# receiver.net
KiCad netlist of a schematic drawn in EAGLE
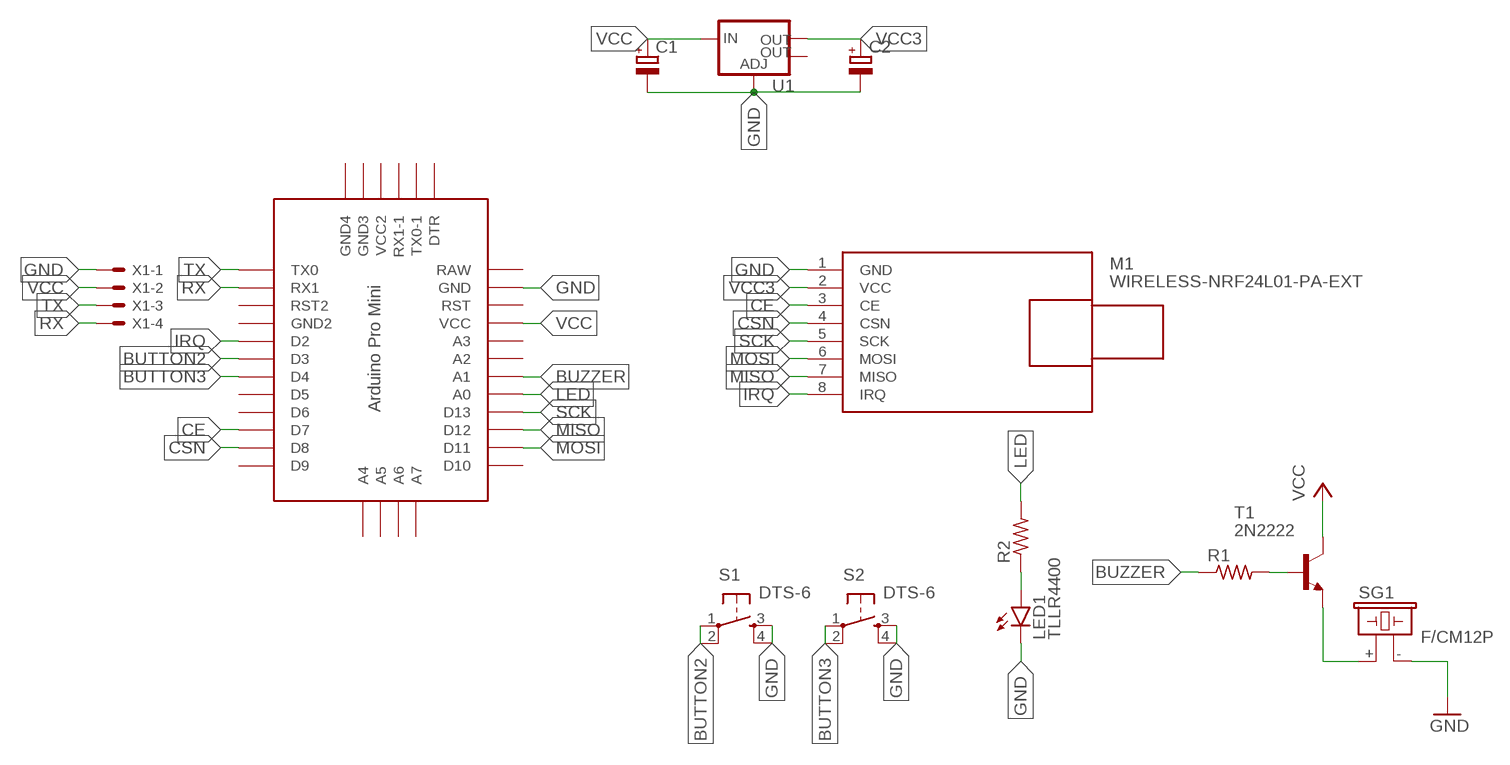
[diagram p0: schematic, sheet 1]

(export (version "E")
  (design (tool "Eeschema 10.0.6"))
  (components
    (comp (ref "C1")
      (value "CPOL-EUE2,5-6E")
      (footprint "eagle-import:E2,5-6E")
      (libsource (lib "eagle-import") (part "CPOL-EUE2,5-6E"))
    )
    (comp (ref "C2")
      (value "CPOL-EUE2,5-6E")
      (footprint "eagle-import:E2,5-6E")
      (libsource (lib "eagle-import") (part "CPOL-EUE2,5-6E"))
    )
    (comp (ref "LED1")
      (value "TLLR4400")
      (footprint "eagle-import:LED3MM")
      (fields (field (name "MF") "VISHAY SEMICONDUCTOR"))
      (libsource (lib "eagle-import") (part "TLLR4400"))
    )
    (comp (ref "M1")
      (value "WIRELESS-NRF24L01-PA-EXT")
      (footprint "eagle-import:WIRELESS-NRF24L01-PA-EXT")
      (libsource (lib "eagle-import") (part "WIRELESS-NRF24L01-PA-EXT"))
    )
    (comp (ref "R1")
      (value "R-US_R0805")
      (footprint "eagle-import:R0805")
      (libsource (lib "eagle-import") (part "R-US_R0805"))
    )
    (comp (ref "R2")
      (value "R-US_R0805")
      (footprint "eagle-import:R0805")
      (libsource (lib "eagle-import") (part "R-US_R0805"))
    )
    (comp (ref "S1")
      (value "DTS-6")
      (footprint "eagle-import:DTS-6")
      (libsource (lib "eagle-import") (part "DTS-6"))
    )
    (comp (ref "S2")
      (value "DTS-6")
      (footprint "eagle-import:DTS-6")
      (libsource (lib "eagle-import") (part "DTS-6"))
    )
    (comp (ref "SG1")
      (value "F/CM12P")
      (footprint "eagle-import:F_CM12P")
      (libsource (lib "eagle-import") (part "F/CM12P"))
    )
    (comp (ref "T1")
      (value "2N2222")
      (footprint "eagle-import:TO92-EBC-OVAL")
      (libsource (lib "eagle-import") (part "2N2222"))
    )
    (comp (ref "U$1")
      (value "PRO-MINI")
      (footprint "eagle-import:PRO-MINI")
      (libsource (lib "eagle-import") (part "PRO-MINI"))
    )
    (comp (ref "U1")
      (value "V_REG_LM1117SOT223")
      (footprint "eagle-import:SOT223")
      (libsource (lib "eagle-import") (part "V_REG_LM1117SOT223"))
    )
    (comp (ref "X1")
      (value "KK-156-4")
      (footprint "eagle-import:KK-156-4")
      (fields (field (name "MF") "MOLEX"))
      (libsource (lib "eagle-import") (part "KK-156-4"))
    )
  )
  (nets
    (net (code "1") (name "/RAW") (class "Default")
      (node (ref "U$1") (pin "RAW") (pinfunction "RAW_RAW") (pintype "power_in"))
    )
    (net (code "2") (name "BUTTON2") (class "Default")
      (node (ref "S1") (pin "1") (pinfunction "1_1") (pintype "passive"))
      (node (ref "S1") (pin "2") (pinfunction "2_2") (pintype "passive"))
      (node (ref "U$1") (pin "D3") (pinfunction "D3_D3") (pintype "bidirectional"))
    )
    (net (code "3") (name "BUTTON3") (class "Default")
      (node (ref "S2") (pin "1") (pinfunction "1_1") (pintype "passive"))
      (node (ref "S2") (pin "2") (pinfunction "2_2") (pintype "passive"))
      (node (ref "U$1") (pin "D4") (pinfunction "D4_D4") (pintype "bidirectional"))
    )
    (net (code "4") (name "BUZZER") (class "Default")
      (node (ref "R1") (pin "1") (pinfunction "1_1") (pintype "passive"))
      (node (ref "U$1") (pin "A1") (pinfunction "A1_A1") (pintype "bidirectional"))
    )
    (net (code "5") (name "CE") (class "Default")
      (node (ref "M1") (pin "3") (pinfunction "CE_3") (pintype "bidirectional"))
      (node (ref "U$1") (pin "D7") (pinfunction "D7_D7") (pintype "bidirectional"))
    )
    (net (code "6") (name "CSN") (class "Default")
      (node (ref "M1") (pin "4") (pinfunction "CSN_4") (pintype "bidirectional"))
      (node (ref "U$1") (pin "D8") (pinfunction "D8_D8") (pintype "bidirectional"))
    )
    (net (code "7") (name "GND") (class "Default")
      (node (ref "C1") (pin "-") (pinfunction "-_-") (pintype "passive"))
      (node (ref "C2") (pin "-") (pinfunction "-_-") (pintype "passive"))
      (node (ref "LED1") (pin "K") (pinfunction "C_K") (pintype "passive"))
      (node (ref "M1") (pin "1") (pinfunction "GND_1") (pintype "power_in"))
      (node (ref "S1") (pin "3") (pinfunction "3_3") (pintype "passive"))
      (node (ref "S1") (pin "4") (pinfunction "4_4") (pintype "passive"))
      (node (ref "S2") (pin "3") (pinfunction "3_3") (pintype "passive"))
      (node (ref "S2") (pin "4") (pinfunction "4_4") (pintype "passive"))
      (node (ref "SG1") (pin "-") (pinfunction "2_-") (pintype "passive"))
      (node (ref "U$1") (pin "GND") (pinfunction "GND_GND") (pintype "input"))
      (node (ref "U1") (pin "1") (pinfunction "ADJ_1") (pintype "input"))
      (node (ref "X1") (pin "1") (pinfunction "S_1") (pintype "passive"))
    )
    (net (code "8") (name "IRQ") (class "Default")
      (node (ref "M1") (pin "8") (pinfunction "IRQ_8") (pintype "bidirectional"))
      (node (ref "U$1") (pin "D2") (pinfunction "D2_D2") (pintype "bidirectional"))
    )
    (net (code "9") (name "LED") (class "Default")
      (node (ref "R2") (pin "2") (pinfunction "2_2") (pintype "passive"))
      (node (ref "U$1") (pin "A0") (pinfunction "A0_A0") (pintype "bidirectional"))
    )
    (net (code "10") (name "MISO") (class "Default")
      (node (ref "M1") (pin "7") (pinfunction "MISO_7") (pintype "bidirectional"))
      (node (ref "U$1") (pin "D12") (pinfunction "D12_D12") (pintype "bidirectional"))
    )
    (net (code "11") (name "MOSI") (class "Default")
      (node (ref "M1") (pin "6") (pinfunction "MOSI_6") (pintype "bidirectional"))
      (node (ref "U$1") (pin "D11") (pinfunction "D11_D11") (pintype "bidirectional"))
    )
    (net (code "12") (name "Net-(LED1-PadA)") (class "Default")
      (node (ref "LED1") (pin "A") (pinfunction "A_A") (pintype "passive"))
      (node (ref "R2") (pin "1") (pinfunction "1_1") (pintype "passive"))
    )
    (net (code "13") (name "Net-(R1-Pad2)") (class "Default")
      (node (ref "R1") (pin "2") (pinfunction "2_2") (pintype "passive"))
      (node (ref "T1") (pin "B") (pinfunction "B_B") (pintype "passive"))
    )
    (net (code "14") (name "Net-(SG1-1)") (class "Default")
      (node (ref "SG1") (pin "+") (pinfunction "1_+") (pintype "passive"))
      (node (ref "T1") (pin "E") (pinfunction "E_E") (pintype "passive"))
    )
    (net (code "15") (name "RX") (class "Default")
      (node (ref "U$1") (pin "RX1") (pinfunction "RX1_RX1") (pintype "bidirectional"))
      (node (ref "X1") (pin "4") (pinfunction "S_4") (pintype "passive"))
    )
    (net (code "16") (name "SCK") (class "Default")
      (node (ref "M1") (pin "5") (pinfunction "SCK_5") (pintype "bidirectional"))
      (node (ref "U$1") (pin "D13") (pinfunction "D13_D13") (pintype "bidirectional"))
    )
    (net (code "17") (name "TX") (class "Default")
      (node (ref "U$1") (pin "TX0") (pinfunction "TX0_TX0") (pintype "bidirectional"))
      (node (ref "X1") (pin "3") (pinfunction "S_3") (pintype "passive"))
    )
    (net (code "18") (name "VCC") (class "Default")
      (node (ref "C1") (pin "+") (pinfunction "+_+") (pintype "passive"))
      (node (ref "T1") (pin "C") (pinfunction "C_C") (pintype "passive"))
      (node (ref "U$1") (pin "VCC") (pinfunction "VCC_VCC") (pintype "bidirectional"))
      (node (ref "U1") (pin "3") (pinfunction "IN_3") (pintype "input"))
      (node (ref "X1") (pin "2") (pinfunction "S_2") (pintype "passive"))
    )
    (net (code "19") (name "VCC3") (class "Default")
      (node (ref "C2") (pin "+") (pinfunction "+_+") (pintype "passive"))
      (node (ref "M1") (pin "2") (pinfunction "VCC_2") (pintype "power_in"))
      (node (ref "U1") (pin "2") (pinfunction "OUT_2") (pintype "output"))
    )
    (net (code "20") (name "unconnected-(U$1-GND2-PadGND1)") (class "Default")
      (node (ref "U$1") (pin "GND1") (pinfunction "GND2_GND1") (pintype "bidirectional"))
    )
    (net (code "21") (name "unconnected-(U$1-GND4-PadGND2)") (class "Default")
      (node (ref "U$1") (pin "GND2") (pinfunction "GND4_GND2") (pintype "bidirectional"))
    )
    (net (code "22") (name "unconnected-(U$1-PadA2)") (class "Default")
      (node (ref "U$1") (pin "A2") (pinfunction "A2_A2") (pintype "bidirectional"))
    )
    (net (code "23") (name "unconnected-(U$1-PadA3)") (class "Default")
      (node (ref "U$1") (pin "A3") (pinfunction "A3_A3") (pintype "bidirectional"))
    )
    (net (code "24") (name "unconnected-(U$1-PadA4)") (class "Default")
      (node (ref "U$1") (pin "A4") (pinfunction "A4_A4") (pintype "bidirectional"))
    )
    (net (code "25") (name "unconnected-(U$1-PadA5)") (class "Default")
      (node (ref "U$1") (pin "A5") (pinfunction "A5_A5") (pintype "bidirectional"))
    )
    (net (code "26") (name "unconnected-(U$1-PadA6)") (class "Default")
      (node (ref "U$1") (pin "A6") (pinfunction "A6_A6") (pintype "bidirectional"))
    )
    (net (code "27") (name "unconnected-(U$1-PadA7)") (class "Default")
      (node (ref "U$1") (pin "A7") (pinfunction "A7_A7") (pintype "bidirectional"))
    )
    (net (code "28") (name "unconnected-(U$1-PadD5)") (class "Default")
      (node (ref "U$1") (pin "D5") (pinfunction "D5_D5") (pintype "bidirectional"))
    )
    (net (code "29") (name "unconnected-(U$1-PadD6)") (class "Default")
      (node (ref "U$1") (pin "D6") (pinfunction "D6_D6") (pintype "bidirectional"))
    )
    (net (code "30") (name "unconnected-(U$1-PadD9)") (class "Default")
      (node (ref "U$1") (pin "D9") (pinfunction "D9_D9") (pintype "bidirectional"))
    )
    (net (code "31") (name "unconnected-(U$1-PadD10)") (class "Default")
      (node (ref "U$1") (pin "D10") (pinfunction "D10_D10") (pintype "bidirectional"))
    )
    (net (code "32") (name "unconnected-(U$1-PadDTR)") (class "Default")
      (node (ref "U$1") (pin "DTR") (pinfunction "DTR_DTR") (pintype "bidirectional"))
    )
    (net (code "33") (name "unconnected-(U$1-PadGND3)") (class "Default")
      (node (ref "U$1") (pin "GND3") (pinfunction "GND3_GND3") (pintype "bidirectional"))
    )
    (net (code "34") (name "unconnected-(U$1-PadRST)") (class "Default")
      (node (ref "U$1") (pin "RST") (pinfunction "RST_RST") (pintype "bidirectional"))
    )
    (net (code "35") (name "unconnected-(U$1-PadRX1-1)") (class "Default")
      (node (ref "U$1") (pin "RX1-1") (pinfunction "RX1-1_RX1-1") (pintype "bidirectional"))
    )
    (net (code "36") (name "unconnected-(U$1-PadTX0-1)") (class "Default")
      (node (ref "U$1") (pin "TX0-1") (pinfunction "TX0-1_TX0-1") (pintype "bidirectional"))
    )
    (net (code "37") (name "unconnected-(U$1-RST2-PadRST1)") (class "Default")
      (node (ref "U$1") (pin "RST1") (pinfunction "RST2_RST1") (pintype "bidirectional"))
    )
    (net (code "38") (name "unconnected-(U$1-VCC2-PadVCC1)") (class "Default")
      (node (ref "U$1") (pin "VCC1") (pinfunction "VCC2_VCC1") (pintype "bidirectional"))
    )
    (net (code "39") (name "unconnected-(U1-OUT-Pad4)") (class "Default")
      (node (ref "U1") (pin "4") (pinfunction "OUT_4") (pintype "output"))
    )
  )
)
